# 2_waffling60-NMB_matrix.net
KiCad netlist of a schematic drawn in Altium Designer
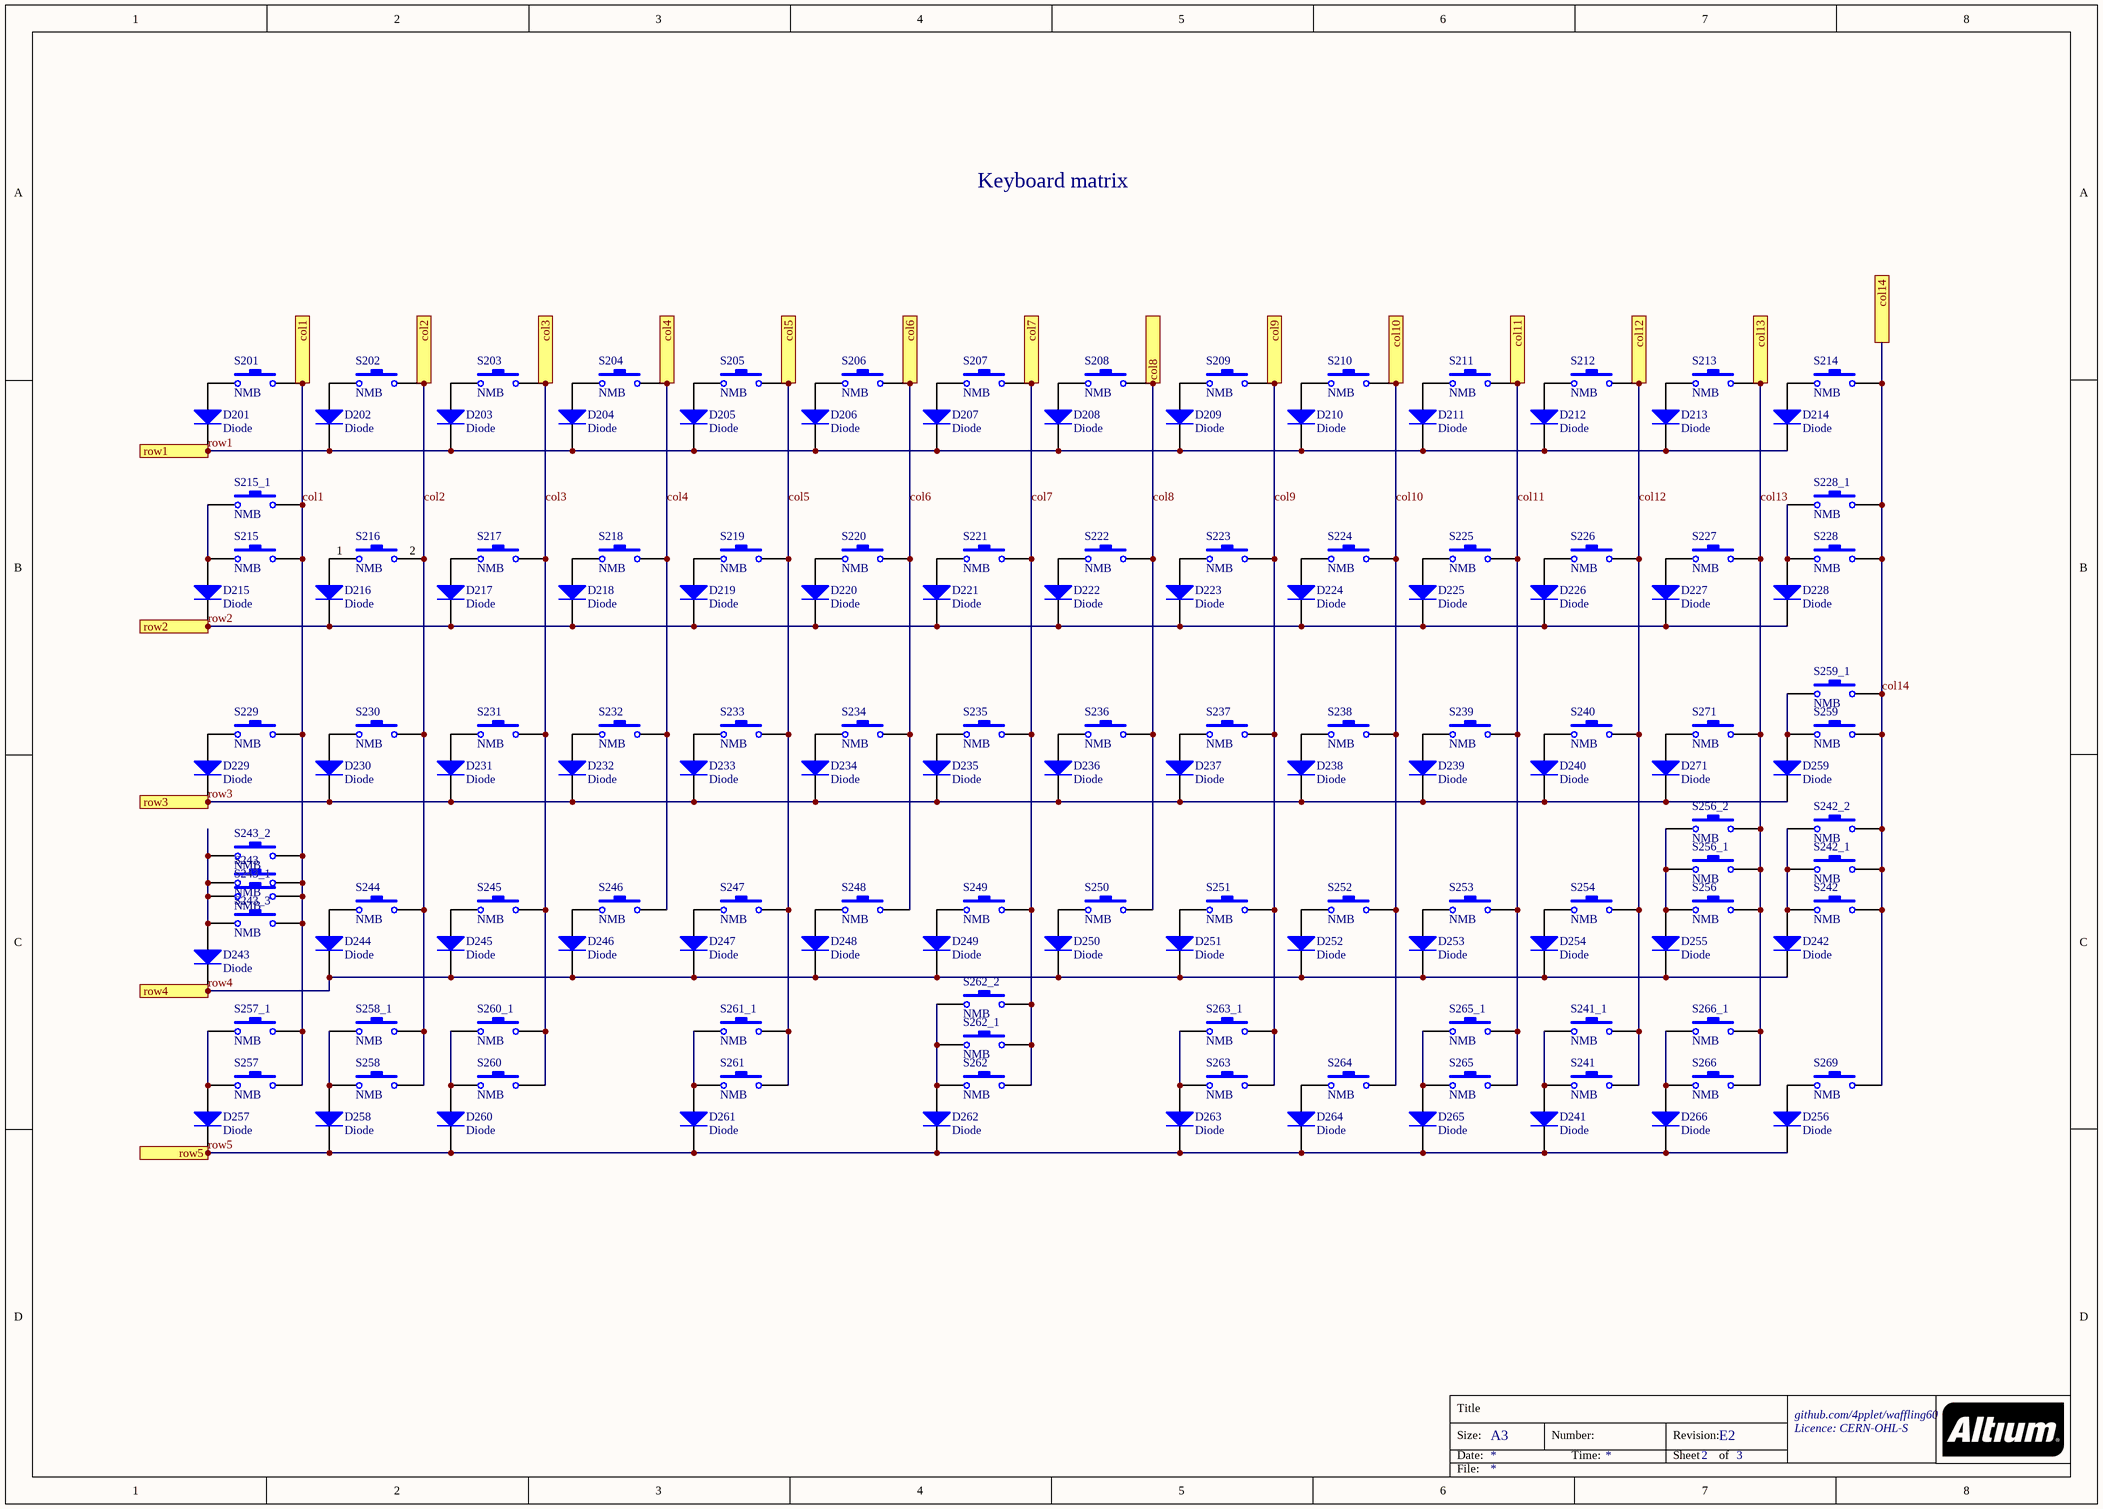
[diagram p0: 2_waffling60-NMB_matrix.SchDoc]

(export (version "E")
  (design (tool "Eeschema 10.0.6"))
  (components
    (comp (ref "D201")
      (value "Diode")
      (footprint "SOD-123")
      (description "Default Diode")
      (fields (field (name "LCSC PART #") "C81598") (field (name "MRF.PART") "1N4148W"))
      (libsource (lib "Miscellaneous Devices") (part "Diode"))
    )
    (comp (ref "D202")
      (value "Diode")
      (footprint "SOD-123")
      (description "Default Diode")
      (fields (field (name "LCSC PART #") "C81598") (field (name "MRF.PART") "1N4148W"))
      (libsource (lib "Miscellaneous Devices") (part "Diode"))
    )
    (comp (ref "D203")
      (value "Diode")
      (footprint "SOD-123")
      (description "Default Diode")
      (fields (field (name "LCSC PART #") "C81598") (field (name "MRF.PART") "1N4148W"))
      (libsource (lib "Miscellaneous Devices") (part "Diode"))
    )
    (comp (ref "D204")
      (value "Diode")
      (footprint "SOD-123")
      (description "Default Diode")
      (fields (field (name "LCSC PART #") "C81598") (field (name "MRF.PART") "1N4148W"))
      (libsource (lib "Miscellaneous Devices") (part "Diode"))
    )
    (comp (ref "D205")
      (value "Diode")
      (footprint "SOD-123")
      (description "Default Diode")
      (fields (field (name "LCSC PART #") "C81598") (field (name "MRF.PART") "1N4148W"))
      (libsource (lib "Miscellaneous Devices") (part "Diode"))
    )
    (comp (ref "D206")
      (value "Diode")
      (footprint "SOD-123")
      (description "Default Diode")
      (fields (field (name "LCSC PART #") "C81598") (field (name "MRF.PART") "1N4148W"))
      (libsource (lib "Miscellaneous Devices") (part "Diode"))
    )
    (comp (ref "D207")
      (value "Diode")
      (footprint "SOD-123")
      (description "Default Diode")
      (fields (field (name "LCSC PART #") "C81598") (field (name "MRF.PART") "1N4148W"))
      (libsource (lib "Miscellaneous Devices") (part "Diode"))
    )
    (comp (ref "D208")
      (value "Diode")
      (footprint "SOD-123")
      (description "Default Diode")
      (fields (field (name "LCSC PART #") "C81598") (field (name "MRF.PART") "1N4148W"))
      (libsource (lib "Miscellaneous Devices") (part "Diode"))
    )
    (comp (ref "D209")
      (value "Diode")
      (footprint "SOD-123")
      (description "Default Diode")
      (fields (field (name "LCSC PART #") "C81598") (field (name "MRF.PART") "1N4148W"))
      (libsource (lib "Miscellaneous Devices") (part "Diode"))
    )
    (comp (ref "D210")
      (value "Diode")
      (footprint "SOD-123")
      (description "Default Diode")
      (fields (field (name "LCSC PART #") "C81598") (field (name "MRF.PART") "1N4148W"))
      (libsource (lib "Miscellaneous Devices") (part "Diode"))
    )
    (comp (ref "D211")
      (value "Diode")
      (footprint "SOD-123")
      (description "Default Diode")
      (fields (field (name "LCSC PART #") "C81598") (field (name "MRF.PART") "1N4148W"))
      (libsource (lib "Miscellaneous Devices") (part "Diode"))
    )
    (comp (ref "D212")
      (value "Diode")
      (footprint "SOD-123")
      (description "Default Diode")
      (fields (field (name "LCSC PART #") "C81598") (field (name "MRF.PART") "1N4148W"))
      (libsource (lib "Miscellaneous Devices") (part "Diode"))
    )
    (comp (ref "D213")
      (value "Diode")
      (footprint "SOD-123")
      (description "Default Diode")
      (fields (field (name "LCSC PART #") "C81598") (field (name "MRF.PART") "1N4148W"))
      (libsource (lib "Miscellaneous Devices") (part "Diode"))
    )
    (comp (ref "D214")
      (value "Diode")
      (footprint "SOD-123")
      (description "Default Diode")
      (fields (field (name "LCSC PART #") "C81598") (field (name "MRF.PART") "1N4148W"))
      (libsource (lib "Miscellaneous Devices") (part "Diode"))
    )
    (comp (ref "D215")
      (value "Diode")
      (footprint "SOD-123")
      (description "Default Diode")
      (fields (field (name "LCSC PART #") "C81598") (field (name "MRF.PART") "1N4148W"))
      (libsource (lib "Miscellaneous Devices") (part "Diode"))
    )
    (comp (ref "D216")
      (value "Diode")
      (footprint "SOD-123")
      (description "Default Diode")
      (fields (field (name "LCSC PART #") "C81598") (field (name "MRF.PART") "1N4148W"))
      (libsource (lib "Miscellaneous Devices") (part "Diode"))
    )
    (comp (ref "D217")
      (value "Diode")
      (footprint "SOD-123")
      (description "Default Diode")
      (fields (field (name "LCSC PART #") "C81598") (field (name "MRF.PART") "1N4148W"))
      (libsource (lib "Miscellaneous Devices") (part "Diode"))
    )
    (comp (ref "D218")
      (value "Diode")
      (footprint "SOD-123")
      (description "Default Diode")
      (fields (field (name "LCSC PART #") "C81598") (field (name "MRF.PART") "1N4148W"))
      (libsource (lib "Miscellaneous Devices") (part "Diode"))
    )
    (comp (ref "D219")
      (value "Diode")
      (footprint "SOD-123")
      (description "Default Diode")
      (fields (field (name "LCSC PART #") "C81598") (field (name "MRF.PART") "1N4148W"))
      (libsource (lib "Miscellaneous Devices") (part "Diode"))
    )
    (comp (ref "D220")
      (value "Diode")
      (footprint "SOD-123")
      (description "Default Diode")
      (fields (field (name "LCSC PART #") "C81598") (field (name "MRF.PART") "1N4148W"))
      (libsource (lib "Miscellaneous Devices") (part "Diode"))
    )
    (comp (ref "D221")
      (value "Diode")
      (footprint "SOD-123")
      (description "Default Diode")
      (fields (field (name "LCSC PART #") "C81598") (field (name "MRF.PART") "1N4148W"))
      (libsource (lib "Miscellaneous Devices") (part "Diode"))
    )
    (comp (ref "D222")
      (value "Diode")
      (footprint "SOD-123")
      (description "Default Diode")
      (fields (field (name "LCSC PART #") "C81598") (field (name "MRF.PART") "1N4148W"))
      (libsource (lib "Miscellaneous Devices") (part "Diode"))
    )
    (comp (ref "D223")
      (value "Diode")
      (footprint "SOD-123")
      (description "Default Diode")
      (fields (field (name "LCSC PART #") "C81598") (field (name "MRF.PART") "1N4148W"))
      (libsource (lib "Miscellaneous Devices") (part "Diode"))
    )
    (comp (ref "D224")
      (value "Diode")
      (footprint "SOD-123")
      (description "Default Diode")
      (fields (field (name "LCSC PART #") "C81598") (field (name "MRF.PART") "1N4148W"))
      (libsource (lib "Miscellaneous Devices") (part "Diode"))
    )
    (comp (ref "D225")
      (value "Diode")
      (footprint "SOD-123")
      (description "Default Diode")
      (fields (field (name "LCSC PART #") "C81598") (field (name "MRF.PART") "1N4148W"))
      (libsource (lib "Miscellaneous Devices") (part "Diode"))
    )
    (comp (ref "D226")
      (value "Diode")
      (footprint "SOD-123")
      (description "Default Diode")
      (fields (field (name "LCSC PART #") "C81598") (field (name "MRF.PART") "1N4148W"))
      (libsource (lib "Miscellaneous Devices") (part "Diode"))
    )
    (comp (ref "D227")
      (value "Diode")
      (footprint "SOD-123")
      (description "Default Diode")
      (fields (field (name "LCSC PART #") "C81598") (field (name "MRF.PART") "1N4148W"))
      (libsource (lib "Miscellaneous Devices") (part "Diode"))
    )
    (comp (ref "D228")
      (value "Diode")
      (footprint "SOD-123")
      (description "Default Diode")
      (fields (field (name "LCSC PART #") "C81598") (field (name "MRF.PART") "1N4148W"))
      (libsource (lib "Miscellaneous Devices") (part "Diode"))
    )
    (comp (ref "D229")
      (value "Diode")
      (footprint "SOD-123")
      (description "Default Diode")
      (fields (field (name "LCSC PART #") "C81598") (field (name "MRF.PART") "1N4148W"))
      (libsource (lib "Miscellaneous Devices") (part "Diode"))
    )
    (comp (ref "D230")
      (value "Diode")
      (footprint "SOD-123")
      (description "Default Diode")
      (fields (field (name "LCSC PART #") "C81598") (field (name "MRF.PART") "1N4148W"))
      (libsource (lib "Miscellaneous Devices") (part "Diode"))
    )
    (comp (ref "D231")
      (value "Diode")
      (footprint "SOD-123")
      (description "Default Diode")
      (fields (field (name "LCSC PART #") "C81598") (field (name "MRF.PART") "1N4148W"))
      (libsource (lib "Miscellaneous Devices") (part "Diode"))
    )
    (comp (ref "D232")
      (value "Diode")
      (footprint "SOD-123")
      (description "Default Diode")
      (fields (field (name "LCSC PART #") "C81598") (field (name "MRF.PART") "1N4148W"))
      (libsource (lib "Miscellaneous Devices") (part "Diode"))
    )
    (comp (ref "D233")
      (value "Diode")
      (footprint "SOD-123")
      (description "Default Diode")
      (fields (field (name "LCSC PART #") "C81598") (field (name "MRF.PART") "1N4148W"))
      (libsource (lib "Miscellaneous Devices") (part "Diode"))
    )
    (comp (ref "D234")
      (value "Diode")
      (footprint "SOD-123")
      (description "Default Diode")
      (fields (field (name "LCSC PART #") "C81598") (field (name "MRF.PART") "1N4148W"))
      (libsource (lib "Miscellaneous Devices") (part "Diode"))
    )
    (comp (ref "D235")
      (value "Diode")
      (footprint "SOD-123")
      (description "Default Diode")
      (fields (field (name "LCSC PART #") "C81598") (field (name "MRF.PART") "1N4148W"))
      (libsource (lib "Miscellaneous Devices") (part "Diode"))
    )
    (comp (ref "D236")
      (value "Diode")
      (footprint "SOD-123")
      (description "Default Diode")
      (fields (field (name "LCSC PART #") "C81598") (field (name "MRF.PART") "1N4148W"))
      (libsource (lib "Miscellaneous Devices") (part "Diode"))
    )
    (comp (ref "D237")
      (value "Diode")
      (footprint "SOD-123")
      (description "Default Diode")
      (fields (field (name "LCSC PART #") "C81598") (field (name "MRF.PART") "1N4148W"))
      (libsource (lib "Miscellaneous Devices") (part "Diode"))
    )
    (comp (ref "D238")
      (value "Diode")
      (footprint "SOD-123")
      (description "Default Diode")
      (fields (field (name "LCSC PART #") "C81598") (field (name "MRF.PART") "1N4148W"))
      (libsource (lib "Miscellaneous Devices") (part "Diode"))
    )
    (comp (ref "D239")
      (value "Diode")
      (footprint "SOD-123")
      (description "Default Diode")
      (fields (field (name "LCSC PART #") "C81598") (field (name "MRF.PART") "1N4148W"))
      (libsource (lib "Miscellaneous Devices") (part "Diode"))
    )
    (comp (ref "D240")
      (value "Diode")
      (footprint "SOD-123")
      (description "Default Diode")
      (fields (field (name "LCSC PART #") "C81598") (field (name "MRF.PART") "1N4148W"))
      (libsource (lib "Miscellaneous Devices") (part "Diode"))
    )
    (comp (ref "D241")
      (value "Diode")
      (footprint "SOD-123")
      (description "Default Diode")
      (fields (field (name "LCSC PART #") "C81598") (field (name "MRF.PART") "1N4148W"))
      (libsource (lib "Miscellaneous Devices") (part "Diode"))
    )
    (comp (ref "D242")
      (value "Diode")
      (footprint "SOD-123")
      (description "Default Diode")
      (fields (field (name "LCSC PART #") "C81598") (field (name "MRF.PART") "1N4148W"))
      (libsource (lib "Miscellaneous Devices") (part "Diode"))
    )
    (comp (ref "D243")
      (value "Diode")
      (footprint "SOD-123")
      (description "Default Diode")
      (fields (field (name "LCSC PART #") "C81598") (field (name "MRF.PART") "1N4148W"))
      (libsource (lib "Miscellaneous Devices") (part "Diode"))
    )
    (comp (ref "D244")
      (value "Diode")
      (footprint "SOD-123")
      (description "Default Diode")
      (fields (field (name "LCSC PART #") "C81598") (field (name "MRF.PART") "1N4148W"))
      (libsource (lib "Miscellaneous Devices") (part "Diode"))
    )
    (comp (ref "D245")
      (value "Diode")
      (footprint "SOD-123")
      (description "Default Diode")
      (fields (field (name "LCSC PART #") "C81598") (field (name "MRF.PART") "1N4148W"))
      (libsource (lib "Miscellaneous Devices") (part "Diode"))
    )
    (comp (ref "D246")
      (value "Diode")
      (footprint "SOD-123")
      (description "Default Diode")
      (fields (field (name "LCSC PART #") "C81598") (field (name "MRF.PART") "1N4148W"))
      (libsource (lib "Miscellaneous Devices") (part "Diode"))
    )
    (comp (ref "D247")
      (value "Diode")
      (footprint "SOD-123")
      (description "Default Diode")
      (fields (field (name "LCSC PART #") "C81598") (field (name "MRF.PART") "1N4148W"))
      (libsource (lib "Miscellaneous Devices") (part "Diode"))
    )
    (comp (ref "D248")
      (value "Diode")
      (footprint "SOD-123")
      (description "Default Diode")
      (fields (field (name "LCSC PART #") "C81598") (field (name "MRF.PART") "1N4148W"))
      (libsource (lib "Miscellaneous Devices") (part "Diode"))
    )
    (comp (ref "D249")
      (value "Diode")
      (footprint "SOD-123")
      (description "Default Diode")
      (fields (field (name "LCSC PART #") "C81598") (field (name "MRF.PART") "1N4148W"))
      (libsource (lib "Miscellaneous Devices") (part "Diode"))
    )
    (comp (ref "D250")
      (value "Diode")
      (footprint "SOD-123")
      (description "Default Diode")
      (fields (field (name "LCSC PART #") "C81598") (field (name "MRF.PART") "1N4148W"))
      (libsource (lib "Miscellaneous Devices") (part "Diode"))
    )
    (comp (ref "D251")
      (value "Diode")
      (footprint "SOD-123")
      (description "Default Diode")
      (fields (field (name "LCSC PART #") "C81598") (field (name "MRF.PART") "1N4148W"))
      (libsource (lib "Miscellaneous Devices") (part "Diode"))
    )
    (comp (ref "D252")
      (value "Diode")
      (footprint "SOD-123")
      (description "Default Diode")
      (fields (field (name "LCSC PART #") "C81598") (field (name "MRF.PART") "1N4148W"))
      (libsource (lib "Miscellaneous Devices") (part "Diode"))
    )
    (comp (ref "D253")
      (value "Diode")
      (footprint "SOD-123")
      (description "Default Diode")
      (fields (field (name "LCSC PART #") "C81598") (field (name "MRF.PART") "1N4148W"))
      (libsource (lib "Miscellaneous Devices") (part "Diode"))
    )
    (comp (ref "D254")
      (value "Diode")
      (footprint "SOD-123")
      (description "Default Diode")
      (fields (field (name "LCSC PART #") "C81598") (field (name "MRF.PART") "1N4148W"))
      (libsource (lib "Miscellaneous Devices") (part "Diode"))
    )
    (comp (ref "D255")
      (value "Diode")
      (footprint "SOD-123")
      (description "Default Diode")
      (fields (field (name "LCSC PART #") "C81598") (field (name "MRF.PART") "1N4148W"))
      (libsource (lib "Miscellaneous Devices") (part "Diode"))
    )
    (comp (ref "D256")
      (value "Diode")
      (footprint "SOD-123")
      (description "Default Diode")
      (fields (field (name "LCSC PART #") "C81598") (field (name "MRF.PART") "1N4148W"))
      (libsource (lib "Miscellaneous Devices") (part "Diode"))
    )
    (comp (ref "D257")
      (value "Diode")
      (footprint "SOD-123")
      (description "Default Diode")
      (fields (field (name "LCSC PART #") "C81598") (field (name "MRF.PART") "1N4148W"))
      (libsource (lib "Miscellaneous Devices") (part "Diode"))
    )
    (comp (ref "D258")
      (value "Diode")
      (footprint "SOD-123")
      (description "Default Diode")
      (fields (field (name "LCSC PART #") "C81598") (field (name "MRF.PART") "1N4148W"))
      (libsource (lib "Miscellaneous Devices") (part "Diode"))
    )
    (comp (ref "D259")
      (value "Diode")
      (footprint "SOD-123")
      (description "Default Diode")
      (fields (field (name "LCSC PART #") "C81598") (field (name "MRF.PART") "1N4148W"))
      (libsource (lib "Miscellaneous Devices") (part "Diode"))
    )
    (comp (ref "D260")
      (value "Diode")
      (footprint "SOD-123")
      (description "Default Diode")
      (fields (field (name "LCSC PART #") "C81598") (field (name "MRF.PART") "1N4148W"))
      (libsource (lib "Miscellaneous Devices") (part "Diode"))
    )
    (comp (ref "D261")
      (value "Diode")
      (footprint "SOD-123")
      (description "Default Diode")
      (fields (field (name "LCSC PART #") "C81598") (field (name "MRF.PART") "1N4148W"))
      (libsource (lib "Miscellaneous Devices") (part "Diode"))
    )
    (comp (ref "D262")
      (value "Diode")
      (footprint "SOD-123")
      (description "Default Diode")
      (fields (field (name "LCSC PART #") "C81598") (field (name "MRF.PART") "1N4148W"))
      (libsource (lib "Miscellaneous Devices") (part "Diode"))
    )
    (comp (ref "D263")
      (value "Diode")
      (footprint "SOD-123")
      (description "Default Diode")
      (fields (field (name "LCSC PART #") "C81598") (field (name "MRF.PART") "1N4148W"))
      (libsource (lib "Miscellaneous Devices") (part "Diode"))
    )
    (comp (ref "D264")
      (value "Diode")
      (footprint "SOD-123")
      (description "Default Diode")
      (fields (field (name "LCSC PART #") "C81598") (field (name "MRF.PART") "1N4148W"))
      (libsource (lib "Miscellaneous Devices") (part "Diode"))
    )
    (comp (ref "D265")
      (value "Diode")
      (footprint "SOD-123")
      (description "Default Diode")
      (fields (field (name "LCSC PART #") "C81598") (field (name "MRF.PART") "1N4148W"))
      (libsource (lib "Miscellaneous Devices") (part "Diode"))
    )
    (comp (ref "D266")
      (value "Diode")
      (footprint "SOD-123")
      (description "Default Diode")
      (fields (field (name "LCSC PART #") "C81598") (field (name "MRF.PART") "1N4148W"))
      (libsource (lib "Miscellaneous Devices") (part "Diode"))
    )
    (comp (ref "D271")
      (value "Diode")
      (footprint "SOD-123")
      (description "Default Diode")
      (fields (field (name "LCSC PART #") "C81598") (field (name "MRF.PART") "1N4148W"))
      (libsource (lib "Miscellaneous Devices") (part "Diode"))
    )
    (comp (ref "S201")
      (value "NMB")
      (footprint "NMB-Switch 1U - switched pol  - no allignment pins")
      (description "Switch")
      (libsource (lib "Miscellaneous Devices") (part "SW-PB"))
    )
    (comp (ref "S202")
      (value "NMB")
      (footprint "NMB-Switch 1U - no allignment pins")
      (description "Switch")
      (libsource (lib "Miscellaneous Devices") (part "SW-PB"))
    )
    (comp (ref "S203")
      (value "NMB")
      (footprint "NMB-Switch 1U - switched pol  - no allignment pins")
      (description "Switch")
      (libsource (lib "Miscellaneous Devices") (part "SW-PB"))
    )
    (comp (ref "S204")
      (value "NMB")
      (footprint "NMB-Switch 1U - switched pol  - no allignment pins")
      (description "Switch")
      (libsource (lib "Miscellaneous Devices") (part "SW-PB"))
    )
    (comp (ref "S205")
      (value "NMB")
      (footprint "NMB-Switch 1U - switched pol  - no allignment pins")
      (description "Switch")
      (libsource (lib "Miscellaneous Devices") (part "SW-PB"))
    )
    (comp (ref "S206")
      (value "NMB")
      (footprint "NMB-Switch 1U - switched pol  - no allignment pins")
      (description "Switch")
      (libsource (lib "Miscellaneous Devices") (part "SW-PB"))
    )
    (comp (ref "S207")
      (value "NMB")
      (footprint "NMB-Switch 1U - switched pol  - no allignment pins")
      (description "Switch")
      (libsource (lib "Miscellaneous Devices") (part "SW-PB"))
    )
    (comp (ref "S208")
      (value "NMB")
      (footprint "NMB-Switch 1U - switched pol  - no allignment pins")
      (description "Switch")
      (libsource (lib "Miscellaneous Devices") (part "SW-PB"))
    )
    (comp (ref "S209")
      (value "NMB")
      (footprint "NMB-Switch 1U - switched pol  - no allignment pins")
      (description "Switch")
      (libsource (lib "Miscellaneous Devices") (part "SW-PB"))
    )
    (comp (ref "S210")
      (value "NMB")
      (footprint "NMB-Switch 1U - switched pol  - no allignment pins")
      (description "Switch")
      (libsource (lib "Miscellaneous Devices") (part "SW-PB"))
    )
    (comp (ref "S211")
      (value "NMB")
      (footprint "NMB-Switch 1U - switched pol  - no allignment pins")
      (description "Switch")
      (libsource (lib "Miscellaneous Devices") (part "SW-PB"))
    )
    (comp (ref "S212")
      (value "NMB")
      (footprint "NMB-Switch 1U - switched pol  - no allignment pins")
      (description "Switch")
      (libsource (lib "Miscellaneous Devices") (part "SW-PB"))
    )
    (comp (ref "S213")
      (value "NMB")
      (footprint "NMB-Switch 1U - switched pol  - no allignment pins")
      (description "Switch")
      (libsource (lib "Miscellaneous Devices") (part "SW-PB"))
    )
    (comp (ref "S214")
      (value "NMB")
      (footprint "NMB-Switch 1U - no allignment pins")
      (description "Switch")
      (libsource (lib "Miscellaneous Devices") (part "SW-PB"))
    )
    (comp (ref "S215")
      (value "NMB")
      (footprint "NMB-Switch 1U - switched pol  - no allignment pins")
      (description "TAB")
      (libsource (lib "Miscellaneous Devices") (part "SW-PB"))
    )
    (comp (ref "S215_1")
      (value "NMB")
      (footprint "NMB-Switch 1U - switched pol  - no allignment pins")
      (description "TAB")
      (libsource (lib "Miscellaneous Devices") (part "SW-PB"))
    )
    (comp (ref "S216")
      (value "NMB")
      (footprint "NMB-Switch 1U - no allignment pins")
      (description "Switch")
      (libsource (lib "") (part "SW-PB_2"))
    )
    (comp (ref "S217")
      (value "NMB")
      (footprint "NMB-Switch 1U - switched pol  - no allignment pins")
      (description "Switch")
      (libsource (lib "Miscellaneous Devices") (part "SW-PB"))
    )
    (comp (ref "S218")
      (value "NMB")
      (footprint "NMB-Switch 1U - switched pol  - no allignment pins")
      (description "Switch")
      (libsource (lib "Miscellaneous Devices") (part "SW-PB"))
    )
    (comp (ref "S219")
      (value "NMB")
      (footprint "NMB-Switch 1U - switched pol  - no allignment pins")
      (description "Switch")
      (libsource (lib "Miscellaneous Devices") (part "SW-PB"))
    )
    (comp (ref "S220")
      (value "NMB")
      (footprint "NMB-Switch 1U - no allignment pins")
      (description "Switch")
      (libsource (lib "Miscellaneous Devices") (part "SW-PB"))
    )
    (comp (ref "S221")
      (value "NMB")
      (footprint "NMB-Switch 1U - switched pol  - no allignment pins")
      (description "Switch")
      (libsource (lib "Miscellaneous Devices") (part "SW-PB"))
    )
    (comp (ref "S222")
      (value "NMB")
      (footprint "NMB-Switch 1U - no allignment pins")
      (description "Switch")
      (libsource (lib "Miscellaneous Devices") (part "SW-PB"))
    )
    (comp (ref "S223")
      (value "NMB")
      (footprint "NMB-Switch 1U - switched pol  - no allignment pins")
      (description "Switch")
      (libsource (lib "Miscellaneous Devices") (part "SW-PB"))
    )
    (comp (ref "S224")
      (value "NMB")
      (footprint "NMB-Switch 1U - switched pol  - no allignment pins")
      (description "Switch")
      (libsource (lib "Miscellaneous Devices") (part "SW-PB"))
    )
    (comp (ref "S225")
      (value "NMB")
      (footprint "NMB-Switch 1U - switched pol  - no allignment pins")
      (description "Switch")
      (libsource (lib "Miscellaneous Devices") (part "SW-PB"))
    )
    (comp (ref "S226")
      (value "NMB")
      (footprint "NMB-Switch 1U - no allignment pins")
      (description "Switch")
      (libsource (lib "Miscellaneous Devices") (part "SW-PB"))
    )
    (comp (ref "S227")
      (value "NMB")
      (footprint "NMB-Switch 1U - no allignment pins")
      (description "Switch")
      (libsource (lib "Miscellaneous Devices") (part "SW-PB"))
    )
    (comp (ref "S228")
      (value "NMB")
      (footprint "NMB-Switch 1U - no allignment pins")
      (description "Switch")
      (libsource (lib "Miscellaneous Devices") (part "SW-PB"))
    )
    (comp (ref "S228_1")
      (value "NMB")
      (footprint "NMB-Switch 1U - no allignment pins")
      (description "Switch")
      (libsource (lib "Miscellaneous Devices") (part "SW-PB"))
    )
    (comp (ref "S229")
      (value "NMB")
      (footprint "NMB-Switch 1U - no allignment pins")
      (description "Switch")
      (libsource (lib "Miscellaneous Devices") (part "SW-PB"))
    )
    (comp (ref "S230")
      (value "NMB")
      (footprint "NMB-Switch 1U - no allignment pins")
      (description "Switch")
      (libsource (lib "Miscellaneous Devices") (part "SW-PB"))
    )
    (comp (ref "S231")
      (value "NMB")
      (footprint "NMB-Switch 1U - switched pol  - no allignment pins")
      (description "Switch")
      (libsource (lib "Miscellaneous Devices") (part "SW-PB"))
    )
    (comp (ref "S232")
      (value "NMB")
      (footprint "NMB-Switch 1U - switched pol  - no allignment pins")
      (description "Switch")
      (libsource (lib "Miscellaneous Devices") (part "SW-PB"))
    )
    (comp (ref "S233")
      (value "NMB")
      (footprint "NMB-Switch 1U - switched pol  - no allignment pins")
      (description "Switch")
      (libsource (lib "Miscellaneous Devices") (part "SW-PB"))
    )
    (comp (ref "S234")
      (value "NMB")
      (footprint "NMB-Switch 1U - switched pol  - no allignment pins")
      (description "Switch")
      (libsource (lib "Miscellaneous Devices") (part "SW-PB"))
    )
    (comp (ref "S235")
      (value "NMB")
      (footprint "NMB-Switch 1U - switched pol  - no allignment pins")
      (description "Switch")
      (libsource (lib "Miscellaneous Devices") (part "SW-PB"))
    )
    (comp (ref "S236")
      (value "NMB")
      (footprint "NMB-Switch 1U - switched pol  - no allignment pins")
      (description "Switch")
      (libsource (lib "Miscellaneous Devices") (part "SW-PB"))
    )
    (comp (ref "S237")
      (value "NMB")
      (footprint "NMB-Switch 1U - switched pol  - no allignment pins")
      (description "Switch")
      (libsource (lib "Miscellaneous Devices") (part "SW-PB"))
    )
    (comp (ref "S238")
      (value "NMB")
      (footprint "NMB-Switch 1U - switched pol  - no allignment pins")
      (description "Switch")
      (libsource (lib "Miscellaneous Devices") (part "SW-PB"))
    )
    (comp (ref "S239")
      (value "NMB")
      (footprint "NMB-Switch 1U - switched pol  - no allignment pins")
      (description "Switch")
      (libsource (lib "Miscellaneous Devices") (part "SW-PB"))
    )
    (comp (ref "S240")
      (value "NMB")
      (footprint "NMB-Switch 1U - switched pol  - no allignment pins")
      (description "Switch")
      (libsource (lib "Miscellaneous Devices") (part "SW-PB"))
    )
    (comp (ref "S241")
      (value "NMB")
      (footprint "NMB-Switch 1U - no allignment pins")
      (description "Switch")
      (libsource (lib "Miscellaneous Devices") (part "SW-PB"))
    )
    (comp (ref "S241_1")
      (value "NMB")
      (footprint "NMB-Switch 1U - no allignment pins")
      (description "Switch")
      (libsource (lib "Miscellaneous Devices") (part "SW-PB"))
    )
    (comp (ref "S242")
      (value "NMB")
      (footprint "NMB-Switch 1U - switched pol  - no allignment pins")
      (description "Switch")
      (libsource (lib "Miscellaneous Devices") (part "SW-PB"))
    )
    (comp (ref "S242_1")
      (value "NMB")
      (footprint "NMB-Switch 1U - no allignment pins")
      (description "Switch")
      (libsource (lib "Miscellaneous Devices") (part "SW-PB"))
    )
    (comp (ref "S242_2")
      (value "NMB")
      (footprint "NMB-Switch 1U - switched pol  - no allignment pins")
      (description "Switch")
      (libsource (lib "Miscellaneous Devices") (part "SW-PB"))
    )
    (comp (ref "S243")
      (value "NMB")
      (footprint "NMB-Switch 1U - switched pol  - no allignment pins")
      (description "Switch")
      (libsource (lib "Miscellaneous Devices") (part "SW-PB"))
    )
    (comp (ref "S243_1")
      (value "NMB")
      (footprint "NMB-Switch 1U - switched pol  - no allignment pins")
      (description "Switch")
      (libsource (lib "Miscellaneous Devices") (part "SW-PB"))
    )
    (comp (ref "S243_2")
      (value "NMB")
      (footprint "NMB-Switch 1U - no allignment pins")
      (description "Switch")
      (libsource (lib "Miscellaneous Devices") (part "SW-PB"))
    )
    (comp (ref "S243_3")
      (value "NMB")
      (footprint "NMB-Switch 1U - no allignment pins")
      (description "Switch")
      (libsource (lib "Miscellaneous Devices") (part "SW-PB"))
    )
    (comp (ref "S244")
      (value "NMB")
      (footprint "NMB-Switch 1U - no allignment pins")
      (description "Switch")
      (libsource (lib "Miscellaneous Devices") (part "SW-PB"))
    )
    (comp (ref "S245")
      (value "NMB")
      (footprint "NMB-Switch 1U - switched pol  - no allignment pins")
      (description "Switch")
      (libsource (lib "Miscellaneous Devices") (part "SW-PB"))
    )
    (comp (ref "S246")
      (value "NMB")
      (footprint "NMB-Switch 1U - switched pol  - no allignment pins")
      (description "Switch")
      (libsource (lib "Miscellaneous Devices") (part "SW-PB"))
    )
    (comp (ref "S247")
      (value "NMB")
      (footprint "NMB-Switch 1U - switched pol  - no allignment pins")
      (description "Switch")
      (libsource (lib "Miscellaneous Devices") (part "SW-PB"))
    )
    (comp (ref "S248")
      (value "NMB")
      (footprint "NMB-Switch 1U - switched pol  - no allignment pins")
      (description "Switch")
      (libsource (lib "Miscellaneous Devices") (part "SW-PB"))
    )
    (comp (ref "S249")
      (value "NMB")
      (footprint "NMB-Switch 1U - switched pol  - no allignment pins")
      (description "Switch")
      (libsource (lib "Miscellaneous Devices") (part "SW-PB"))
    )
    (comp (ref "S250")
      (value "NMB")
      (footprint "NMB-Switch 1U - switched pol  - no allignment pins")
      (description "Switch")
      (libsource (lib "Miscellaneous Devices") (part "SW-PB"))
    )
    (comp (ref "S251")
      (value "NMB")
      (footprint "NMB-Switch 1U - switched pol  - no allignment pins")
      (description "Switch")
      (libsource (lib "Miscellaneous Devices") (part "SW-PB"))
    )
    (comp (ref "S252")
      (value "NMB")
      (footprint "NMB-Switch 1U - switched pol  - no allignment pins")
      (description "Switch")
      (libsource (lib "Miscellaneous Devices") (part "SW-PB"))
    )
    (comp (ref "S253")
      (value "NMB")
      (footprint "NMB-Switch 1U - switched pol  - no allignment pins")
      (description "Switch")
      (libsource (lib "Miscellaneous Devices") (part "SW-PB"))
    )
    (comp (ref "S254")
      (value "NMB")
      (footprint "NMB-Switch 1U - switched pol  - no allignment pins")
      (description "Switch")
      (libsource (lib "Miscellaneous Devices") (part "SW-PB"))
    )
    (comp (ref "S256")
      (value "NMB")
      (footprint "NMB-Switch 1U - switched pol  - no allignment pins")
      (description "Switch")
      (libsource (lib "Miscellaneous Devices") (part "SW-PB"))
    )
    (comp (ref "S256_1")
      (value "NMB")
      (footprint "NMB-Switch 1U - switched pol  - no allignment pins")
      (description "Switch")
      (libsource (lib "Miscellaneous Devices") (part "SW-PB"))
    )
    (comp (ref "S256_2")
      (value "NMB")
      (footprint "NMB-Switch 1U - no allignment pins")
      (description "Switch")
      (libsource (lib "Miscellaneous Devices") (part "SW-PB"))
    )
    (comp (ref "S257")
      (value "NMB")
      (footprint "NMB-Switch 1U - no allignment pins")
      (description "Switch")
      (libsource (lib "Miscellaneous Devices") (part "SW-PB"))
    )
    (comp (ref "S257_1")
      (value "NMB")
      (footprint "NMB-Switch 1U - no allignment pins")
      (description "Switch")
      (libsource (lib "Miscellaneous Devices") (part "SW-PB"))
    )
    (comp (ref "S258")
      (value "NMB")
      (footprint "NMB-Switch 1U - no allignment pins")
      (description "Switch")
      (libsource (lib "Miscellaneous Devices") (part "SW-PB"))
    )
    (comp (ref "S258_1")
      (value "NMB")
      (footprint "NMB-Switch 1U - no allignment pins")
      (description "Switch")
      (libsource (lib "Miscellaneous Devices") (part "SW-PB"))
    )
    (comp (ref "S259")
      (value "NMB")
      (footprint "NMB-Switch 1U - no allignment pins")
      (description "Switch")
      (libsource (lib "") (part "SW-PB_1"))
    )
    (comp (ref "S259_1")
      (value "NMB")
      (footprint "NMB-Switch 1U - no allignment pins")
      (description "Switch")
      (libsource (lib "Miscellaneous Devices") (part "SW-PB"))
    )
    (comp (ref "S260")
      (value "NMB")
      (footprint "NMB-Switch 1U - no allignment pins")
      (description "Switch")
      (libsource (lib "Miscellaneous Devices") (part "SW-PB"))
    )
    (comp (ref "S260_1")
      (value "NMB")
      (footprint "NMB-Switch 1U - no allignment pins")
      (description "Switch")
      (libsource (lib "Miscellaneous Devices") (part "SW-PB"))
    )
    (comp (ref "S261")
      (value "NMB")
      (footprint "NMB-Switch 1U - no allignment pins")
      (description "Switch")
      (libsource (lib "Miscellaneous Devices") (part "SW-PB"))
    )
    (comp (ref "S261_1")
      (value "NMB")
      (footprint "NMB-Switch 1U - no allignment pins")
      (description "Switch")
      (libsource (lib "Miscellaneous Devices") (part "SW-PB"))
    )
    (comp (ref "S262")
      (value "NMB")
      (footprint "NMB-Switch 1U - no allignment pins")
      (description "Switch")
      (libsource (lib "Miscellaneous Devices") (part "SW-PB"))
    )
    (comp (ref "S262_1")
      (value "NMB")
      (footprint "NMB-Switch 1U - no allignment pins")
      (description "Switch")
      (libsource (lib "Miscellaneous Devices") (part "SW-PB"))
    )
    (comp (ref "S262_2")
      (value "NMB")
      (footprint "NMB-Switch 1U - no allignment pins")
      (description "Switch")
      (libsource (lib "Miscellaneous Devices") (part "SW-PB"))
    )
    (comp (ref "S263")
      (value "NMB")
      (footprint "NMB-Switch 1U - no allignment pins")
      (description "Switch")
      (libsource (lib "Miscellaneous Devices") (part "SW-PB"))
    )
    (comp (ref "S263_1")
      (value "NMB")
      (footprint "NMB-Switch 1U - no allignment pins")
      (description "Switch")
      (libsource (lib "Miscellaneous Devices") (part "SW-PB"))
    )
    (comp (ref "S264")
      (value "NMB")
      (footprint "NMB-Switch 1U - switched pol  - no allignment pins")
      (description "Switch")
      (libsource (lib "Miscellaneous Devices") (part "SW-PB"))
    )
    (comp (ref "S265")
      (value "NMB")
      (footprint "NMB-Switch 1U - no allignment pins")
      (description "Switch")
      (libsource (lib "Miscellaneous Devices") (part "SW-PB"))
    )
    (comp (ref "S265_1")
      (value "NMB")
      (footprint "NMB-Switch 1U - no allignment pins")
      (description "Switch")
      (libsource (lib "Miscellaneous Devices") (part "SW-PB"))
    )
    (comp (ref "S266")
      (value "NMB")
      (footprint "NMB-Switch 1U - no allignment pins")
      (description "Switch")
      (libsource (lib "Miscellaneous Devices") (part "SW-PB"))
    )
    (comp (ref "S266_1")
      (value "NMB")
      (footprint "NMB-Switch 1U - no allignment pins")
      (description "Switch")
      (libsource (lib "Miscellaneous Devices") (part "SW-PB"))
    )
    (comp (ref "S269")
      (value "NMB")
      (footprint "NMB-Switch 1U - no allignment pins")
      (description "Switch")
      (libsource (lib "Miscellaneous Devices") (part "SW-PB"))
    )
    (comp (ref "S271")
      (value "NMB")
      (footprint "NMB-Switch 1U - no allignment pins")
      (description "Switch")
      (libsource (lib "Miscellaneous Devices") (part "SW-PB"))
    )
  )
  (nets
    (net (code "1") (name "/col1") (class "Default")
      (node (ref "S201") (pin "2") (pinfunction "2_2") (pintype "passive"))
      (node (ref "S215") (pin "2") (pinfunction "2_2") (pintype "passive"))
      (node (ref "S215_1") (pin "2") (pinfunction "2_2") (pintype "passive"))
      (node (ref "S229") (pin "1") (pinfunction "1_1") (pintype "passive"))
      (node (ref "S243") (pin "2") (pinfunction "2_2") (pintype "passive"))
      (node (ref "S243_1") (pin "2") (pinfunction "2_2") (pintype "passive"))
      (node (ref "S243_2") (pin "2") (pinfunction "2_2") (pintype "passive"))
      (node (ref "S243_3") (pin "2") (pinfunction "2_2") (pintype "passive"))
      (node (ref "S257") (pin "1") (pinfunction "1_1") (pintype "passive"))
      (node (ref "S257_1") (pin "1") (pinfunction "1_1") (pintype "passive"))
    )
    (net (code "2") (name "/col2") (class "Default")
      (node (ref "S202") (pin "2") (pinfunction "2_2") (pintype "passive"))
      (node (ref "S216") (pin "2") (pinfunction "2_2") (pintype "passive"))
      (node (ref "S230") (pin "2") (pinfunction "2_2") (pintype "passive"))
      (node (ref "S244") (pin "1") (pinfunction "1_1") (pintype "passive"))
      (node (ref "S258") (pin "2") (pinfunction "2_2") (pintype "passive"))
      (node (ref "S258_1") (pin "1") (pinfunction "1_1") (pintype "passive"))
    )
    (net (code "3") (name "/col3") (class "Default")
      (node (ref "S203") (pin "2") (pinfunction "2_2") (pintype "passive"))
      (node (ref "S217") (pin "2") (pinfunction "2_2") (pintype "passive"))
      (node (ref "S231") (pin "2") (pinfunction "2_2") (pintype "passive"))
      (node (ref "S245") (pin "2") (pinfunction "2_2") (pintype "passive"))
      (node (ref "S260") (pin "2") (pinfunction "2_2") (pintype "passive"))
      (node (ref "S260_1") (pin "1") (pinfunction "1_1") (pintype "passive"))
    )
    (net (code "4") (name "/col4") (class "Default")
      (node (ref "S204") (pin "2") (pinfunction "2_2") (pintype "passive"))
      (node (ref "S218") (pin "2") (pinfunction "2_2") (pintype "passive"))
      (node (ref "S232") (pin "2") (pinfunction "2_2") (pintype "passive"))
      (node (ref "S246") (pin "2") (pinfunction "2_2") (pintype "passive"))
    )
    (net (code "5") (name "/col5") (class "Default")
      (node (ref "S205") (pin "2") (pinfunction "2_2") (pintype "passive"))
      (node (ref "S219") (pin "2") (pinfunction "2_2") (pintype "passive"))
      (node (ref "S233") (pin "2") (pinfunction "2_2") (pintype "passive"))
      (node (ref "S247") (pin "2") (pinfunction "2_2") (pintype "passive"))
      (node (ref "S261") (pin "2") (pinfunction "2_2") (pintype "passive"))
      (node (ref "S261_1") (pin "2") (pinfunction "2_2") (pintype "passive"))
    )
    (net (code "6") (name "/col6") (class "Default")
      (node (ref "S206") (pin "2") (pinfunction "2_2") (pintype "passive"))
      (node (ref "S220") (pin "2") (pinfunction "2_2") (pintype "passive"))
      (node (ref "S234") (pin "2") (pinfunction "2_2") (pintype "passive"))
      (node (ref "S248") (pin "2") (pinfunction "2_2") (pintype "passive"))
    )
    (net (code "7") (name "/col7") (class "Default")
      (node (ref "S207") (pin "2") (pinfunction "2_2") (pintype "passive"))
      (node (ref "S221") (pin "2") (pinfunction "2_2") (pintype "passive"))
      (node (ref "S235") (pin "2") (pinfunction "2_2") (pintype "passive"))
      (node (ref "S249") (pin "2") (pinfunction "2_2") (pintype "passive"))
      (node (ref "S262") (pin "1") (pinfunction "1_1") (pintype "passive"))
      (node (ref "S262_1") (pin "1") (pinfunction "1_1") (pintype "passive"))
      (node (ref "S262_2") (pin "1") (pinfunction "1_1") (pintype "passive"))
    )
    (net (code "8") (name "/col8") (class "Default")
      (node (ref "S208") (pin "2") (pinfunction "2_2") (pintype "passive"))
      (node (ref "S222") (pin "2") (pinfunction "2_2") (pintype "passive"))
      (node (ref "S236") (pin "2") (pinfunction "2_2") (pintype "passive"))
      (node (ref "S250") (pin "2") (pinfunction "2_2") (pintype "passive"))
    )
    (net (code "9") (name "/col9") (class "Default")
      (node (ref "S209") (pin "2") (pinfunction "2_2") (pintype "passive"))
      (node (ref "S223") (pin "2") (pinfunction "2_2") (pintype "passive"))
      (node (ref "S237") (pin "2") (pinfunction "2_2") (pintype "passive"))
      (node (ref "S251") (pin "2") (pinfunction "2_2") (pintype "passive"))
      (node (ref "S263") (pin "1") (pinfunction "1_1") (pintype "passive"))
      (node (ref "S263_1") (pin "1") (pinfunction "1_1") (pintype "passive"))
    )
    (net (code "10") (name "/col10") (class "Default")
      (node (ref "S210") (pin "2") (pinfunction "2_2") (pintype "passive"))
      (node (ref "S224") (pin "2") (pinfunction "2_2") (pintype "passive"))
      (node (ref "S238") (pin "2") (pinfunction "2_2") (pintype "passive"))
      (node (ref "S252") (pin "2") (pinfunction "2_2") (pintype "passive"))
      (node (ref "S264") (pin "2") (pinfunction "2_2") (pintype "passive"))
    )
    (net (code "11") (name "/col11") (class "Default")
      (node (ref "S211") (pin "2") (pinfunction "2_2") (pintype "passive"))
      (node (ref "S225") (pin "2") (pinfunction "2_2") (pintype "passive"))
      (node (ref "S239") (pin "2") (pinfunction "2_2") (pintype "passive"))
      (node (ref "S253") (pin "2") (pinfunction "2_2") (pintype "passive"))
      (node (ref "S265") (pin "1") (pinfunction "1_1") (pintype "passive"))
      (node (ref "S265_1") (pin "1") (pinfunction "1_1") (pintype "passive"))
    )
    (net (code "12") (name "/col12") (class "Default")
      (node (ref "S212") (pin "2") (pinfunction "2_2") (pintype "passive"))
      (node (ref "S226") (pin "2") (pinfunction "2_2") (pintype "passive"))
      (node (ref "S240") (pin "2") (pinfunction "2_2") (pintype "passive"))
      (node (ref "S241") (pin "1") (pinfunction "1_1") (pintype "passive"))
      (node (ref "S241_1") (pin "1") (pinfunction "1_1") (pintype "passive"))
      (node (ref "S254") (pin "2") (pinfunction "2_2") (pintype "passive"))
    )
    (net (code "13") (name "/col13") (class "Default")
      (node (ref "S213") (pin "2") (pinfunction "2_2") (pintype "passive"))
      (node (ref "S227") (pin "2") (pinfunction "2_2") (pintype "passive"))
      (node (ref "S256") (pin "2") (pinfunction "2_2") (pintype "passive"))
      (node (ref "S256_1") (pin "2") (pinfunction "2_2") (pintype "passive"))
      (node (ref "S256_2") (pin "2") (pinfunction "2_2") (pintype "passive"))
      (node (ref "S266") (pin "2") (pinfunction "2_2") (pintype "passive"))
      (node (ref "S266_1") (pin "2") (pinfunction "2_2") (pintype "passive"))
      (node (ref "S271") (pin "2") (pinfunction "2_2") (pintype "passive"))
    )
    (net (code "14") (name "/col14") (class "Default")
      (node (ref "S214") (pin "2") (pinfunction "2_2") (pintype "passive"))
      (node (ref "S228") (pin "2") (pinfunction "2_2") (pintype "passive"))
      (node (ref "S228_1") (pin "2") (pinfunction "2_2") (pintype "passive"))
      (node (ref "S242") (pin "2") (pinfunction "2_2") (pintype "passive"))
      (node (ref "S242_1") (pin "2") (pinfunction "2_2") (pintype "passive"))
      (node (ref "S242_2") (pin "2") (pinfunction "2_2") (pintype "passive"))
      (node (ref "S259") (pin "1") (pinfunction "1_1") (pintype "passive"))
      (node (ref "S259_1") (pin "2") (pinfunction "2_2") (pintype "passive"))
      (node (ref "S269") (pin "2") (pinfunction "2_2") (pintype "passive"))
    )
    (net (code "15") (name "/row1") (class "Default")
      (node (ref "D201") (pin "2") (pinfunction "K_2") (pintype "passive"))
      (node (ref "D202") (pin "2") (pinfunction "K_2") (pintype "passive"))
      (node (ref "D203") (pin "2") (pinfunction "K_2") (pintype "passive"))
      (node (ref "D204") (pin "2") (pinfunction "K_2") (pintype "passive"))
      (node (ref "D205") (pin "2") (pinfunction "K_2") (pintype "passive"))
      (node (ref "D206") (pin "2") (pinfunction "K_2") (pintype "passive"))
      (node (ref "D207") (pin "2") (pinfunction "K_2") (pintype "passive"))
      (node (ref "D208") (pin "2") (pinfunction "K_2") (pintype "passive"))
      (node (ref "D209") (pin "2") (pinfunction "K_2") (pintype "passive"))
      (node (ref "D210") (pin "2") (pinfunction "K_2") (pintype "passive"))
      (node (ref "D211") (pin "2") (pinfunction "K_2") (pintype "passive"))
      (node (ref "D212") (pin "2") (pinfunction "K_2") (pintype "passive"))
      (node (ref "D213") (pin "2") (pinfunction "K_2") (pintype "passive"))
      (node (ref "D214") (pin "2") (pinfunction "K_2") (pintype "passive"))
    )
    (net (code "16") (name "/row2") (class "Default")
      (node (ref "D215") (pin "2") (pinfunction "K_2") (pintype "passive"))
      (node (ref "D216") (pin "2") (pinfunction "K_2") (pintype "passive"))
      (node (ref "D217") (pin "2") (pinfunction "K_2") (pintype "passive"))
      (node (ref "D218") (pin "2") (pinfunction "K_2") (pintype "passive"))
      (node (ref "D219") (pin "2") (pinfunction "K_2") (pintype "passive"))
      (node (ref "D220") (pin "2") (pinfunction "K_2") (pintype "passive"))
      (node (ref "D221") (pin "2") (pinfunction "K_2") (pintype "passive"))
      (node (ref "D222") (pin "2") (pinfunction "K_2") (pintype "passive"))
      (node (ref "D223") (pin "2") (pinfunction "K_2") (pintype "passive"))
      (node (ref "D224") (pin "2") (pinfunction "K_2") (pintype "passive"))
      (node (ref "D225") (pin "2") (pinfunction "K_2") (pintype "passive"))
      (node (ref "D226") (pin "2") (pinfunction "K_2") (pintype "passive"))
      (node (ref "D227") (pin "2") (pinfunction "K_2") (pintype "passive"))
      (node (ref "D228") (pin "2") (pinfunction "K_2") (pintype "passive"))
    )
    (net (code "17") (name "/row3") (class "Default")
      (node (ref "D229") (pin "2") (pinfunction "K_2") (pintype "passive"))
      (node (ref "D230") (pin "2") (pinfunction "K_2") (pintype "passive"))
      (node (ref "D231") (pin "2") (pinfunction "K_2") (pintype "passive"))
      (node (ref "D232") (pin "2") (pinfunction "K_2") (pintype "passive"))
      (node (ref "D233") (pin "2") (pinfunction "K_2") (pintype "passive"))
      (node (ref "D234") (pin "2") (pinfunction "K_2") (pintype "passive"))
      (node (ref "D235") (pin "2") (pinfunction "K_2") (pintype "passive"))
      (node (ref "D236") (pin "2") (pinfunction "K_2") (pintype "passive"))
      (node (ref "D237") (pin "2") (pinfunction "K_2") (pintype "passive"))
      (node (ref "D238") (pin "2") (pinfunction "K_2") (pintype "passive"))
      (node (ref "D239") (pin "2") (pinfunction "K_2") (pintype "passive"))
      (node (ref "D240") (pin "2") (pinfunction "K_2") (pintype "passive"))
      (node (ref "D259") (pin "2") (pinfunction "K_2") (pintype "passive"))
      (node (ref "D271") (pin "2") (pinfunction "K_2") (pintype "passive"))
    )
    (net (code "18") (name "/row4") (class "Default")
      (node (ref "D242") (pin "2") (pinfunction "K_2") (pintype "passive"))
      (node (ref "D243") (pin "2") (pinfunction "K_2") (pintype "passive"))
      (node (ref "D244") (pin "2") (pinfunction "K_2") (pintype "passive"))
      (node (ref "D245") (pin "2") (pinfunction "K_2") (pintype "passive"))
      (node (ref "D246") (pin "2") (pinfunction "K_2") (pintype "passive"))
      (node (ref "D247") (pin "2") (pinfunction "K_2") (pintype "passive"))
      (node (ref "D248") (pin "2") (pinfunction "K_2") (pintype "passive"))
      (node (ref "D249") (pin "2") (pinfunction "K_2") (pintype "passive"))
      (node (ref "D250") (pin "2") (pinfunction "K_2") (pintype "passive"))
      (node (ref "D251") (pin "2") (pinfunction "K_2") (pintype "passive"))
      (node (ref "D252") (pin "2") (pinfunction "K_2") (pintype "passive"))
      (node (ref "D253") (pin "2") (pinfunction "K_2") (pintype "passive"))
      (node (ref "D254") (pin "2") (pinfunction "K_2") (pintype "passive"))
      (node (ref "D255") (pin "2") (pinfunction "K_2") (pintype "passive"))
    )
    (net (code "19") (name "/row5") (class "Default")
      (node (ref "D241") (pin "2") (pinfunction "K_2") (pintype "passive"))
      (node (ref "D256") (pin "2") (pinfunction "K_2") (pintype "passive"))
      (node (ref "D257") (pin "2") (pinfunction "K_2") (pintype "passive"))
      (node (ref "D258") (pin "2") (pinfunction "K_2") (pintype "passive"))
      (node (ref "D260") (pin "2") (pinfunction "K_2") (pintype "passive"))
      (node (ref "D261") (pin "2") (pinfunction "K_2") (pintype "passive"))
      (node (ref "D262") (pin "2") (pinfunction "K_2") (pintype "passive"))
      (node (ref "D263") (pin "2") (pinfunction "K_2") (pintype "passive"))
      (node (ref "D264") (pin "2") (pinfunction "K_2") (pintype "passive"))
      (node (ref "D265") (pin "2") (pinfunction "K_2") (pintype "passive"))
      (node (ref "D266") (pin "2") (pinfunction "K_2") (pintype "passive"))
    )
    (net (code "20") (name "Net-(D201-A)") (class "Default")
      (node (ref "D201") (pin "1") (pinfunction "A_1") (pintype "passive"))
      (node (ref "S201") (pin "1") (pinfunction "1_1") (pintype "passive"))
    )
    (net (code "21") (name "Net-(D202-A)") (class "Default")
      (node (ref "D202") (pin "1") (pinfunction "A_1") (pintype "passive"))
      (node (ref "S202") (pin "1") (pinfunction "1_1") (pintype "passive"))
    )
    (net (code "22") (name "Net-(D203-A)") (class "Default")
      (node (ref "D203") (pin "1") (pinfunction "A_1") (pintype "passive"))
      (node (ref "S203") (pin "1") (pinfunction "1_1") (pintype "passive"))
    )
    (net (code "23") (name "Net-(D204-A)") (class "Default")
      (node (ref "D204") (pin "1") (pinfunction "A_1") (pintype "passive"))
      (node (ref "S204") (pin "1") (pinfunction "1_1") (pintype "passive"))
    )
    (net (code "24") (name "Net-(D205-A)") (class "Default")
      (node (ref "D205") (pin "1") (pinfunction "A_1") (pintype "passive"))
      (node (ref "S205") (pin "1") (pinfunction "1_1") (pintype "passive"))
    )
    (net (code "25") (name "Net-(D206-A)") (class "Default")
      (node (ref "D206") (pin "1") (pinfunction "A_1") (pintype "passive"))
      (node (ref "S206") (pin "1") (pinfunction "1_1") (pintype "passive"))
    )
    (net (code "26") (name "Net-(D207-A)") (class "Default")
      (node (ref "D207") (pin "1") (pinfunction "A_1") (pintype "passive"))
      (node (ref "S207") (pin "1") (pinfunction "1_1") (pintype "passive"))
    )
    (net (code "27") (name "Net-(D208-A)") (class "Default")
      (node (ref "D208") (pin "1") (pinfunction "A_1") (pintype "passive"))
      (node (ref "S208") (pin "1") (pinfunction "1_1") (pintype "passive"))
    )
    (net (code "28") (name "Net-(D209-A)") (class "Default")
      (node (ref "D209") (pin "1") (pinfunction "A_1") (pintype "passive"))
      (node (ref "S209") (pin "1") (pinfunction "1_1") (pintype "passive"))
    )
    (net (code "29") (name "Net-(D210-A)") (class "Default")
      (node (ref "D210") (pin "1") (pinfunction "A_1") (pintype "passive"))
      (node (ref "S210") (pin "1") (pinfunction "1_1") (pintype "passive"))
    )
    (net (code "30") (name "Net-(D211-A)") (class "Default")
      (node (ref "D211") (pin "1") (pinfunction "A_1") (pintype "passive"))
      (node (ref "S211") (pin "1") (pinfunction "1_1") (pintype "passive"))
    )
    (net (code "31") (name "Net-(D212-A)") (class "Default")
      (node (ref "D212") (pin "1") (pinfunction "A_1") (pintype "passive"))
      (node (ref "S212") (pin "1") (pinfunction "1_1") (pintype "passive"))
    )
    (net (code "32") (name "Net-(D213-A)") (class "Default")
      (node (ref "D213") (pin "1") (pinfunction "A_1") (pintype "passive"))
      (node (ref "S213") (pin "1") (pinfunction "1_1") (pintype "passive"))
    )
    (net (code "33") (name "Net-(D214-A)") (class "Default")
      (node (ref "D214") (pin "1") (pinfunction "A_1") (pintype "passive"))
      (node (ref "S214") (pin "1") (pinfunction "1_1") (pintype "passive"))
    )
    (net (code "34") (name "Net-(D215-A)") (class "Default")
      (node (ref "D215") (pin "1") (pinfunction "A_1") (pintype "passive"))
      (node (ref "S215") (pin "1") (pinfunction "1_1") (pintype "passive"))
      (node (ref "S215_1") (pin "1") (pinfunction "1_1") (pintype "passive"))
    )
    (net (code "35") (name "Net-(D216-A)") (class "Default")
      (node (ref "D216") (pin "1") (pinfunction "A_1") (pintype "passive"))
      (node (ref "S216") (pin "1") (pinfunction "1_1") (pintype "passive"))
    )
    (net (code "36") (name "Net-(D217-A)") (class "Default")
      (node (ref "D217") (pin "1") (pinfunction "A_1") (pintype "passive"))
      (node (ref "S217") (pin "1") (pinfunction "1_1") (pintype "passive"))
    )
    (net (code "37") (name "Net-(D218-A)") (class "Default")
      (node (ref "D218") (pin "1") (pinfunction "A_1") (pintype "passive"))
      (node (ref "S218") (pin "1") (pinfunction "1_1") (pintype "passive"))
    )
    (net (code "38") (name "Net-(D219-A)") (class "Default")
      (node (ref "D219") (pin "1") (pinfunction "A_1") (pintype "passive"))
      (node (ref "S219") (pin "1") (pinfunction "1_1") (pintype "passive"))
    )
    (net (code "39") (name "Net-(D220-A)") (class "Default")
      (node (ref "D220") (pin "1") (pinfunction "A_1") (pintype "passive"))
      (node (ref "S220") (pin "1") (pinfunction "1_1") (pintype "passive"))
    )
    (net (code "40") (name "Net-(D221-A)") (class "Default")
      (node (ref "D221") (pin "1") (pinfunction "A_1") (pintype "passive"))
      (node (ref "S221") (pin "1") (pinfunction "1_1") (pintype "passive"))
    )
    (net (code "41") (name "Net-(D222-A)") (class "Default")
      (node (ref "D222") (pin "1") (pinfunction "A_1") (pintype "passive"))
      (node (ref "S222") (pin "1") (pinfunction "1_1") (pintype "passive"))
    )
    (net (code "42") (name "Net-(D223-A)") (class "Default")
      (node (ref "D223") (pin "1") (pinfunction "A_1") (pintype "passive"))
      (node (ref "S223") (pin "1") (pinfunction "1_1") (pintype "passive"))
    )
    (net (code "43") (name "Net-(D224-A)") (class "Default")
      (node (ref "D224") (pin "1") (pinfunction "A_1") (pintype "passive"))
      (node (ref "S224") (pin "1") (pinfunction "1_1") (pintype "passive"))
    )
    (net (code "44") (name "Net-(D225-A)") (class "Default")
      (node (ref "D225") (pin "1") (pinfunction "A_1") (pintype "passive"))
      (node (ref "S225") (pin "1") (pinfunction "1_1") (pintype "passive"))
    )
    (net (code "45") (name "Net-(D226-A)") (class "Default")
      (node (ref "D226") (pin "1") (pinfunction "A_1") (pintype "passive"))
      (node (ref "S226") (pin "1") (pinfunction "1_1") (pintype "passive"))
    )
    (net (code "46") (name "Net-(D227-A)") (class "Default")
      (node (ref "D227") (pin "1") (pinfunction "A_1") (pintype "passive"))
      (node (ref "S227") (pin "1") (pinfunction "1_1") (pintype "passive"))
    )
    (net (code "47") (name "Net-(D228-A)") (class "Default")
      (node (ref "D228") (pin "1") (pinfunction "A_1") (pintype "passive"))
      (node (ref "S228") (pin "1") (pinfunction "1_1") (pintype "passive"))
      (node (ref "S228_1") (pin "1") (pinfunction "1_1") (pintype "passive"))
    )
    (net (code "48") (name "Net-(D229-A)") (class "Default")
      (node (ref "D229") (pin "1") (pinfunction "A_1") (pintype "passive"))
      (node (ref "S229") (pin "2") (pinfunction "2_2") (pintype "passive"))
    )
    (net (code "49") (name "Net-(D230-A)") (class "Default")
      (node (ref "D230") (pin "1") (pinfunction "A_1") (pintype "passive"))
      (node (ref "S230") (pin "1") (pinfunction "1_1") (pintype "passive"))
    )
    (net (code "50") (name "Net-(D231-A)") (class "Default")
      (node (ref "D231") (pin "1") (pinfunction "A_1") (pintype "passive"))
      (node (ref "S231") (pin "1") (pinfunction "1_1") (pintype "passive"))
    )
    (net (code "51") (name "Net-(D232-A)") (class "Default")
      (node (ref "D232") (pin "1") (pinfunction "A_1") (pintype "passive"))
      (node (ref "S232") (pin "1") (pinfunction "1_1") (pintype "passive"))
    )
    (net (code "52") (name "Net-(D233-A)") (class "Default")
      (node (ref "D233") (pin "1") (pinfunction "A_1") (pintype "passive"))
      (node (ref "S233") (pin "1") (pinfunction "1_1") (pintype "passive"))
    )
    (net (code "53") (name "Net-(D234-A)") (class "Default")
      (node (ref "D234") (pin "1") (pinfunction "A_1") (pintype "passive"))
      (node (ref "S234") (pin "1") (pinfunction "1_1") (pintype "passive"))
    )
    (net (code "54") (name "Net-(D235-A)") (class "Default")
      (node (ref "D235") (pin "1") (pinfunction "A_1") (pintype "passive"))
      (node (ref "S235") (pin "1") (pinfunction "1_1") (pintype "passive"))
    )
    (net (code "55") (name "Net-(D236-A)") (class "Default")
      (node (ref "D236") (pin "1") (pinfunction "A_1") (pintype "passive"))
      (node (ref "S236") (pin "1") (pinfunction "1_1") (pintype "passive"))
    )
    (net (code "56") (name "Net-(D237-A)") (class "Default")
      (node (ref "D237") (pin "1") (pinfunction "A_1") (pintype "passive"))
      (node (ref "S237") (pin "1") (pinfunction "1_1") (pintype "passive"))
    )
    (net (code "57") (name "Net-(D238-A)") (class "Default")
      (node (ref "D238") (pin "1") (pinfunction "A_1") (pintype "passive"))
      (node (ref "S238") (pin "1") (pinfunction "1_1") (pintype "passive"))
    )
    (net (code "58") (name "Net-(D239-A)") (class "Default")
      (node (ref "D239") (pin "1") (pinfunction "A_1") (pintype "passive"))
      (node (ref "S239") (pin "1") (pinfunction "1_1") (pintype "passive"))
    )
    (net (code "59") (name "Net-(D240-A)") (class "Default")
      (node (ref "D240") (pin "1") (pinfunction "A_1") (pintype "passive"))
      (node (ref "S240") (pin "1") (pinfunction "1_1") (pintype "passive"))
    )
    (net (code "60") (name "Net-(D241-A)") (class "Default")
      (node (ref "D241") (pin "1") (pinfunction "A_1") (pintype "passive"))
      (node (ref "S241") (pin "2") (pinfunction "2_2") (pintype "passive"))
      (node (ref "S241_1") (pin "2") (pinfunction "2_2") (pintype "passive"))
    )
    (net (code "61") (name "Net-(D242-A)") (class "Default")
      (node (ref "D242") (pin "1") (pinfunction "A_1") (pintype "passive"))
      (node (ref "S242") (pin "1") (pinfunction "1_1") (pintype "passive"))
      (node (ref "S242_1") (pin "1") (pinfunction "1_1") (pintype "passive"))
      (node (ref "S242_2") (pin "1") (pinfunction "1_1") (pintype "passive"))
    )
    (net (code "62") (name "Net-(D243-A)") (class "Default")
      (node (ref "D243") (pin "1") (pinfunction "A_1") (pintype "passive"))
      (node (ref "S243") (pin "1") (pinfunction "1_1") (pintype "passive"))
      (node (ref "S243_1") (pin "1") (pinfunction "1_1") (pintype "passive"))
      (node (ref "S243_2") (pin "1") (pinfunction "1_1") (pintype "passive"))
      (node (ref "S243_3") (pin "1") (pinfunction "1_1") (pintype "passive"))
    )
    (net (code "63") (name "Net-(D244-A)") (class "Default")
      (node (ref "D244") (pin "1") (pinfunction "A_1") (pintype "passive"))
      (node (ref "S244") (pin "2") (pinfunction "2_2") (pintype "passive"))
    )
    (net (code "64") (name "Net-(D245-A)") (class "Default")
      (node (ref "D245") (pin "1") (pinfunction "A_1") (pintype "passive"))
      (node (ref "S245") (pin "1") (pinfunction "1_1") (pintype "passive"))
    )
    (net (code "65") (name "Net-(D246-A)") (class "Default")
      (node (ref "D246") (pin "1") (pinfunction "A_1") (pintype "passive"))
      (node (ref "S246") (pin "1") (pinfunction "1_1") (pintype "passive"))
    )
    (net (code "66") (name "Net-(D247-A)") (class "Default")
      (node (ref "D247") (pin "1") (pinfunction "A_1") (pintype "passive"))
      (node (ref "S247") (pin "1") (pinfunction "1_1") (pintype "passive"))
    )
    (net (code "67") (name "Net-(D248-A)") (class "Default")
      (node (ref "D248") (pin "1") (pinfunction "A_1") (pintype "passive"))
      (node (ref "S248") (pin "1") (pinfunction "1_1") (pintype "passive"))
    )
    (net (code "68") (name "Net-(D249-A)") (class "Default")
      (node (ref "D249") (pin "1") (pinfunction "A_1") (pintype "passive"))
      (node (ref "S249") (pin "1") (pinfunction "1_1") (pintype "passive"))
    )
    (net (code "69") (name "Net-(D250-A)") (class "Default")
      (node (ref "D250") (pin "1") (pinfunction "A_1") (pintype "passive"))
      (node (ref "S250") (pin "1") (pinfunction "1_1") (pintype "passive"))
    )
    (net (code "70") (name "Net-(D251-A)") (class "Default")
      (node (ref "D251") (pin "1") (pinfunction "A_1") (pintype "passive"))
      (node (ref "S251") (pin "1") (pinfunction "1_1") (pintype "passive"))
    )
    (net (code "71") (name "Net-(D252-A)") (class "Default")
      (node (ref "D252") (pin "1") (pinfunction "A_1") (pintype "passive"))
      (node (ref "S252") (pin "1") (pinfunction "1_1") (pintype "passive"))
    )
    (net (code "72") (name "Net-(D253-A)") (class "Default")
      (node (ref "D253") (pin "1") (pinfunction "A_1") (pintype "passive"))
      (node (ref "S253") (pin "1") (pinfunction "1_1") (pintype "passive"))
    )
    (net (code "73") (name "Net-(D254-A)") (class "Default")
      (node (ref "D254") (pin "1") (pinfunction "A_1") (pintype "passive"))
      (node (ref "S254") (pin "1") (pinfunction "1_1") (pintype "passive"))
    )
    (net (code "74") (name "Net-(D255-A)") (class "Default")
      (node (ref "D255") (pin "1") (pinfunction "A_1") (pintype "passive"))
      (node (ref "S256") (pin "1") (pinfunction "1_1") (pintype "passive"))
      (node (ref "S256_1") (pin "1") (pinfunction "1_1") (pintype "passive"))
      (node (ref "S256_2") (pin "1") (pinfunction "1_1") (pintype "passive"))
    )
    (net (code "75") (name "Net-(D256-A)") (class "Default")
      (node (ref "D256") (pin "1") (pinfunction "A_1") (pintype "passive"))
      (node (ref "S269") (pin "1") (pinfunction "1_1") (pintype "passive"))
    )
    (net (code "76") (name "Net-(D257-A)") (class "Default")
      (node (ref "D257") (pin "1") (pinfunction "A_1") (pintype "passive"))
      (node (ref "S257") (pin "2") (pinfunction "2_2") (pintype "passive"))
      (node (ref "S257_1") (pin "2") (pinfunction "2_2") (pintype "passive"))
    )
    (net (code "77") (name "Net-(D258-A)") (class "Default")
      (node (ref "D258") (pin "1") (pinfunction "A_1") (pintype "passive"))
      (node (ref "S258") (pin "1") (pinfunction "1_1") (pintype "passive"))
      (node (ref "S258_1") (pin "2") (pinfunction "2_2") (pintype "passive"))
    )
    (net (code "78") (name "Net-(D259-A)") (class "Default")
      (node (ref "D259") (pin "1") (pinfunction "A_1") (pintype "passive"))
      (node (ref "S259") (pin "1") (pinfunction "1_1") (pintype "passive"))
      (node (ref "S259_1") (pin "1") (pinfunction "1_1") (pintype "passive"))
    )
    (net (code "79") (name "Net-(D260-A)") (class "Default")
      (node (ref "D260") (pin "1") (pinfunction "A_1") (pintype "passive"))
      (node (ref "S260") (pin "1") (pinfunction "1_1") (pintype "passive"))
      (node (ref "S260_1") (pin "2") (pinfunction "2_2") (pintype "passive"))
    )
    (net (code "80") (name "Net-(D261-A)") (class "Default")
      (node (ref "D261") (pin "1") (pinfunction "A_1") (pintype "passive"))
      (node (ref "S261") (pin "1") (pinfunction "1_1") (pintype "passive"))
      (node (ref "S261_1") (pin "1") (pinfunction "1_1") (pintype "passive"))
    )
    (net (code "81") (name "Net-(D262-A)") (class "Default")
      (node (ref "D262") (pin "1") (pinfunction "A_1") (pintype "passive"))
      (node (ref "S262") (pin "2") (pinfunction "2_2") (pintype "passive"))
      (node (ref "S262_1") (pin "2") (pinfunction "2_2") (pintype "passive"))
      (node (ref "S262_2") (pin "2") (pinfunction "2_2") (pintype "passive"))
    )
    (net (code "82") (name "Net-(D263-A)") (class "Default")
      (node (ref "D263") (pin "1") (pinfunction "A_1") (pintype "passive"))
      (node (ref "S263") (pin "2") (pinfunction "2_2") (pintype "passive"))
      (node (ref "S263_1") (pin "2") (pinfunction "2_2") (pintype "passive"))
    )
    (net (code "83") (name "Net-(D264-A)") (class "Default")
      (node (ref "D264") (pin "1") (pinfunction "A_1") (pintype "passive"))
      (node (ref "S264") (pin "1") (pinfunction "1_1") (pintype "passive"))
    )
    (net (code "84") (name "Net-(D265-A)") (class "Default")
      (node (ref "D265") (pin "1") (pinfunction "A_1") (pintype "passive"))
      (node (ref "S265") (pin "2") (pinfunction "2_2") (pintype "passive"))
      (node (ref "S265_1") (pin "2") (pinfunction "2_2") (pintype "passive"))
    )
    (net (code "85") (name "Net-(D266-A)") (class "Default")
      (node (ref "D266") (pin "1") (pinfunction "A_1") (pintype "passive"))
      (node (ref "S266") (pin "1") (pinfunction "1_1") (pintype "passive"))
      (node (ref "S266_1") (pin "1") (pinfunction "1_1") (pintype "passive"))
    )
    (net (code "86") (name "Net-(D271-A)") (class "Default")
      (node (ref "D271") (pin "1") (pinfunction "A_1") (pintype "passive"))
      (node (ref "S271") (pin "1") (pinfunction "1_1") (pintype "passive"))
    )
  )
)
